# System_Clocks.net
KiCad netlist of a schematic drawn in Altium Designer
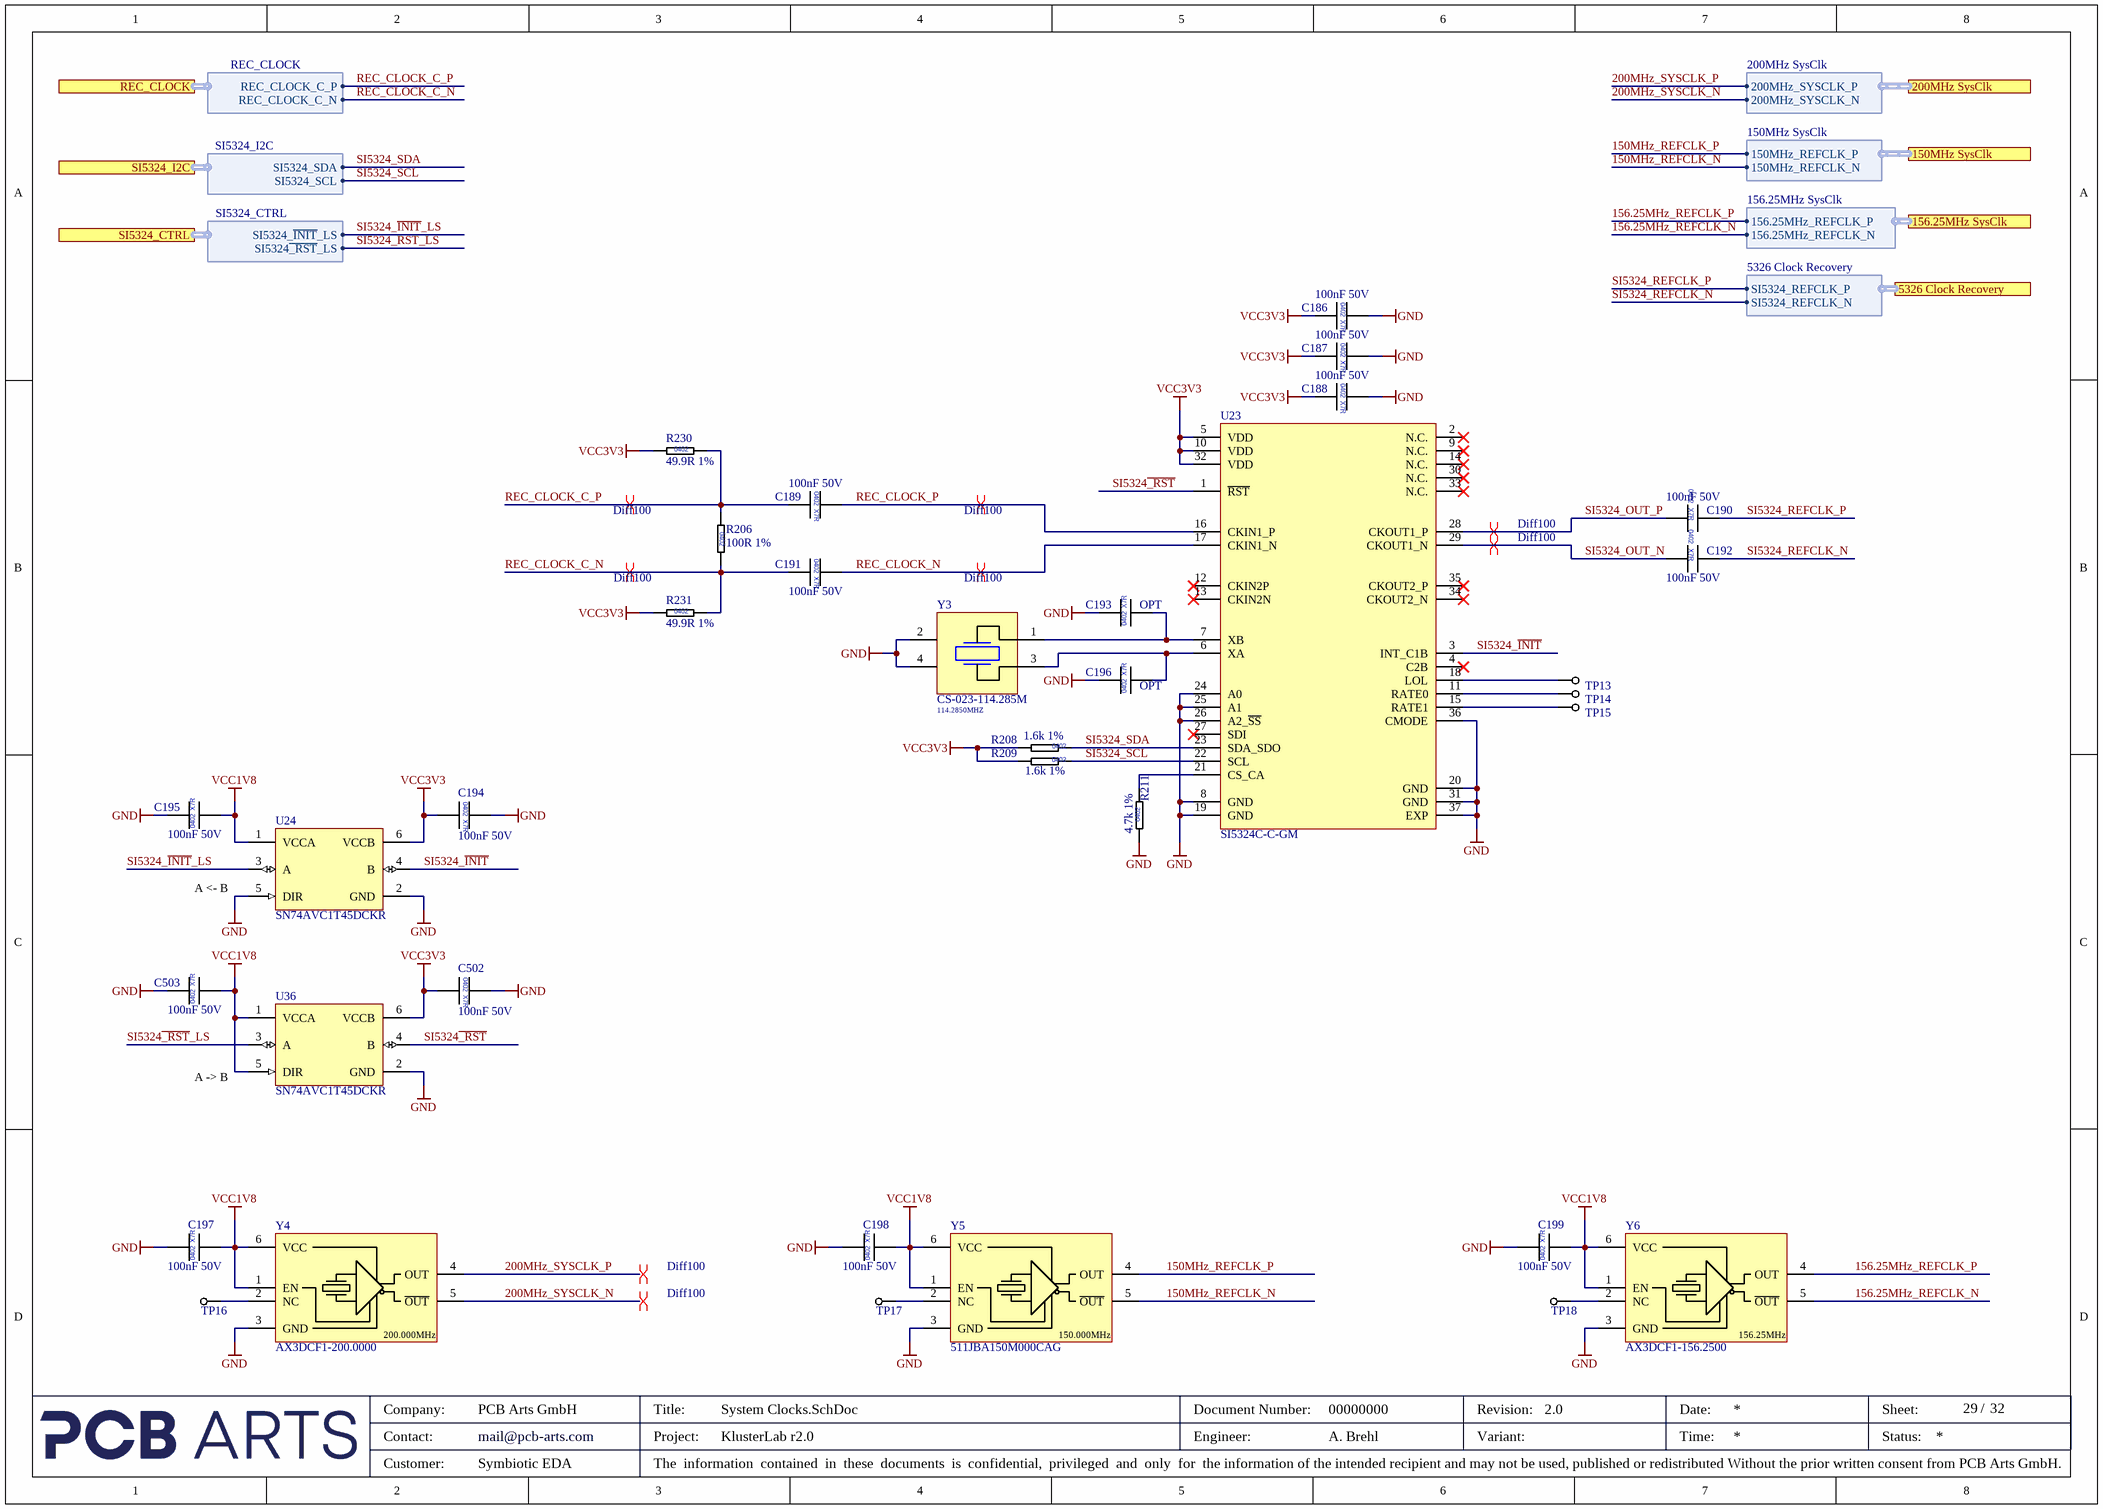
[diagram p0: System Clocks.SchDoc]

(export (version "E")
  (design (tool "Eeschema 10.0.6"))
  (components
    (comp (ref "C186")
      (value "100nF 50V")
      (footprint "Cap:CAP_0402_L")
      (description "Multilayer Ceramic Capacitors MLCC - SMD/SMT 0402 50VDC")
      (libsource (lib "") (part "CAP_0402_100nF_50V_1"))
    )
    (comp (ref "C187")
      (value "100nF 50V")
      (footprint "Cap:CAP_0402_L")
      (description "Multilayer Ceramic Capacitors MLCC - SMD/SMT 0402 50VDC")
      (libsource (lib "") (part "CAP_0402_100nF_50V_1"))
    )
    (comp (ref "C188")
      (value "100nF 50V")
      (footprint "Cap:CAP_0402_L")
      (description "Multilayer Ceramic Capacitors MLCC - SMD/SMT 0402 50VDC")
      (libsource (lib "") (part "CAP_0402_100nF_50V_1"))
    )
    (comp (ref "C189")
      (value "100nF 50V")
      (footprint "Cap:CAP_0402_L")
      (description "Multilayer Ceramic Capacitors MLCC - SMD/SMT 0402 50VDC")
      (libsource (lib "") (part "CAP_0402_100nF_50V_1"))
    )
    (comp (ref "C190")
      (value "100nF 50V")
      (footprint "Cap:CAP_0402_L")
      (description "Multilayer Ceramic Capacitors MLCC - SMD/SMT 0402 50VDC")
      (libsource (lib "Cap") (part "CAP_0402_100nF_50V"))
    )
    (comp (ref "C191")
      (value "100nF 50V")
      (footprint "Cap:CAP_0402_L")
      (description "Multilayer Ceramic Capacitors MLCC - SMD/SMT 0402 50VDC")
      (libsource (lib "") (part "CAP_0402_100nF_50V_1"))
    )
    (comp (ref "C192")
      (value "100nF 50V")
      (footprint "Cap:CAP_0402_L")
      (description "Multilayer Ceramic Capacitors MLCC - SMD/SMT 0402 50VDC")
      (libsource (lib "Cap") (part "CAP_0402_100nF_50V"))
    )
    (comp (ref "C193")
      (value "OPT")
      (footprint "Cap:CAP_0402_L")
      (description "Multilayer Ceramic Capacitors MLCC - SMD/SMT 0402 Optional Placeholder")
      (libsource (lib "Cap") (part "CAP_0402_OPT"))
    )
    (comp (ref "C194")
      (value "100nF 50V")
      (footprint "Cap:CAP_0402_L")
      (description "Multilayer Ceramic Capacitors MLCC - SMD/SMT 0402 50VDC")
      (libsource (lib "") (part "CAP_0402_100nF_50V_1"))
    )
    (comp (ref "C195")
      (value "100nF 50V")
      (footprint "Cap:CAP_0402_L")
      (description "Multilayer Ceramic Capacitors MLCC - SMD/SMT 0402 50VDC")
      (libsource (lib "Cap") (part "CAP_0402_100nF_50V"))
    )
    (comp (ref "C196")
      (value "OPT")
      (footprint "Cap:CAP_0402_L")
      (description "Multilayer Ceramic Capacitors MLCC - SMD/SMT 0402 Optional Placeholder")
      (libsource (lib "Cap") (part "CAP_0402_OPT"))
    )
    (comp (ref "C197")
      (value "100nF 50V")
      (footprint "Cap:CAP_0402_L")
      (description "Multilayer Ceramic Capacitors MLCC - SMD/SMT 0402 50VDC")
      (libsource (lib "Cap") (part "CAP_0402_100nF_50V"))
    )
    (comp (ref "C198")
      (value "100nF 50V")
      (footprint "Cap:CAP_0402_L")
      (description "Multilayer Ceramic Capacitors MLCC - SMD/SMT 0402 50VDC")
      (libsource (lib "Cap") (part "CAP_0402_100nF_50V"))
    )
    (comp (ref "C199")
      (value "100nF 50V")
      (footprint "Cap:CAP_0402_L")
      (description "Multilayer Ceramic Capacitors MLCC - SMD/SMT 0402 50VDC")
      (libsource (lib "Cap") (part "CAP_0402_100nF_50V"))
    )
    (comp (ref "C502")
      (value "100nF 50V")
      (footprint "Cap:CAP_0402_L")
      (description "Multilayer Ceramic Capacitors MLCC - SMD/SMT 0402 50VDC")
      (libsource (lib "") (part "CAP_0402_100nF_50V_1"))
    )
    (comp (ref "C503")
      (value "100nF 50V")
      (footprint "Cap:CAP_0402_L")
      (description "Multilayer Ceramic Capacitors MLCC - SMD/SMT 0402 50VDC")
      (libsource (lib "Cap") (part "CAP_0402_100nF_50V"))
    )
    (comp (ref "R206")
      (value "100R 1%")
      (footprint "Res:RES_0402_L")
      (description "Thick Film Resistors - SMD 100Ohm 1%")
      (libsource (lib "Res") (part "RES_0402_100R_1%"))
    )
    (comp (ref "R208")
      (value "1.6k 1%")
      (footprint "Res:RES_0402_L")
      (description "Thick Film Resistors - SMD 1.6kOhm 1%")
      (libsource (lib "Res") (part "RES_0402_1.6k_1%"))
    )
    (comp (ref "R209")
      (value "1.6k 1%")
      (footprint "Res:RES_0402_L")
      (description "Thick Film Resistors - SMD 1.6kOhm 1%")
      (libsource (lib "Res") (part "RES_0402_1.6k_1%"))
    )
    (comp (ref "R211")
      (value "4.7k 1%")
      (footprint "Res:RES_0402_L")
      (description "Thick Film Resistors - SMD 4.7kOhm 1%")
      (libsource (lib "Res") (part "RES_0402_4.7k_1%"))
    )
    (comp (ref "R230")
      (value "49.9R 1%")
      (footprint "Res:RES_0402_L")
      (description "Thick Film Resistors - SMD 49.9Ohm 1%")
      (libsource (lib "Res") (part "RES_0402_49.9R_1%"))
    )
    (comp (ref "R231")
      (value "49.9R 1%")
      (footprint "Res:RES_0402_L")
      (description "Thick Film Resistors - SMD 49.9Ohm 1%")
      (libsource (lib "Res") (part "RES_0402_49.9R_1%"))
    )
    (comp (ref "TP13")
      (value "Testpoint")
      (footprint "Electro_mech:Testpoint 0.8mm")
      (description "Testpoint 0.8mm")
      (libsource (lib "Electro_Mech") (part "Testpoint 0.8mm"))
    )
    (comp (ref "TP14")
      (value "Testpoint")
      (footprint "Electro_mech:Testpoint 0.8mm")
      (description "Testpoint 0.8mm")
      (libsource (lib "Electro_Mech") (part "Testpoint 0.8mm"))
    )
    (comp (ref "TP15")
      (value "Testpoint")
      (footprint "Electro_mech:Testpoint 0.8mm")
      (description "Testpoint 0.8mm")
      (libsource (lib "Electro_Mech") (part "Testpoint 0.8mm"))
    )
    (comp (ref "TP16")
      (value "Testpoint")
      (footprint "Electro_mech:Testpoint 0.8mm")
      (description "Testpoint 0.8mm")
      (libsource (lib "Electro_Mech") (part "Testpoint 0.8mm"))
    )
    (comp (ref "TP17")
      (value "Testpoint")
      (footprint "Electro_mech:Testpoint 0.8mm")
      (description "Testpoint 0.8mm")
      (libsource (lib "Electro_Mech") (part "Testpoint 0.8mm"))
    )
    (comp (ref "TP18")
      (value "Testpoint")
      (footprint "Electro_mech:Testpoint 0.8mm")
      (description "Testpoint 0.8mm")
      (libsource (lib "Electro_Mech") (part "Testpoint 0.8mm"))
    )
    (comp (ref "U23")
      (value "SI5324C-C-GM")
      (footprint "Timer:QFN50P600X600X85-37N")
      (description "PRECISION CLOCK MULTIPLIER/ JITTER ATTENUATOR")
      (libsource (lib "Timer") (part "SI5324C-C-GM_PRECISION CLOCK MULTIPLIER/ JITTER ATTENUATOR"))
    )
    (comp (ref "U24")
      (value "SN74AVC1T45DCKR")
      (footprint "Digital:SOT65P210X100-6N")
      (description "Single-Bit Dual-Supply Bus Transceiver with Configurable Voltage Translation and 3-State Outputs")
      (libsource (lib "Digital") (part "SN74AVC1T45DCKR_Single-Bit Dual-Supply Bus Transceiver"))
    )
    (comp (ref "U36")
      (value "SN74AVC1T45DCKR")
      (footprint "Digital:SOT65P210X100-6N")
      (description "Single-Bit Dual-Supply Bus Transceiver with Configurable Voltage Translation and 3-State Outputs")
      (libsource (lib "Digital") (part "SN74AVC1T45DCKR_Single-Bit Dual-Supply Bus Transceiver"))
    )
    (comp (ref "Y3")
      (value "CS-023-114.285M")
      (footprint "Timer:S3D - Shenzhen SCTF Elec")
      (description "3.2 x 2.5 x 0.8 mm SMD Crystal")
      (fields (field (name "FREQUENCY") "114.2850MHZ"))
      (libsource (lib "Timer") (part "Quarz 114.2850MHz ESR 80R 18pF"))
    )
    (comp (ref "Y4")
      (value "AX3DCF1-200.0000")
      (footprint "Timer:Abracon AX3")
      (description "200MHz Clock Oscillator, 1V8, LVDS")
      (libsource (lib "Timer") (part "AX3DCF1-200.0000_200MHz Clock Oscillator, 1V8, LVDS"))
    )
    (comp (ref "Y5")
      (value "511JBA150M000CAG")
      (footprint "Timer:Abracon AX3")
      (description "150MHz Clock Oscillator, 1V8, LVDS")
      (libsource (lib "Timer") (part "511JBA150M000CAG_150MHz Clock Oscillator, 1V8, LVDS"))
    )
    (comp (ref "Y6")
      (value "AX3DCF1-156.2500")
      (footprint "Timer:Abracon AX3")
      (description "156.25MHz Clock Oscillator, 1V8, LVDS")
      (libsource (lib "Timer") (part "AX3DCF1-156.2500_156.25MHz Clock Oscillator, 1V8, LVDS"))
    )
  )
  (nets
    (net (code "11") (name "/150MHz_REFCLK_N") (class "Default")
      (node (ref "Y5") (pin "5") (pinfunction "~{OUT}_5") (pintype "passive"))
    )
    (net (code "12") (name "/150MHz_REFCLK_P") (class "Default")
      (node (ref "Y5") (pin "4") (pinfunction "OUT_4") (pintype "passive"))
    )
    (net (code "13") (name "/156.25MHz_REFCLK_N") (class "Default")
      (node (ref "Y6") (pin "5") (pinfunction "~{OUT}_5") (pintype "passive"))
    )
    (net (code "14") (name "/156.25MHz_REFCLK_P") (class "Default")
      (node (ref "Y6") (pin "4") (pinfunction "OUT_4") (pintype "passive"))
    )
    (net (code "15") (name "/200MHz_SYSCLK_N") (class "Default")
      (node (ref "Y4") (pin "5") (pinfunction "~{OUT}_5") (pintype "passive"))
    )
    (net (code "16") (name "/200MHz_SYSCLK_P") (class "Default")
      (node (ref "Y4") (pin "4") (pinfunction "OUT_4") (pintype "passive"))
    )
    (net (code "17") (name "/REC_CLOCK_C_N") (class "Default")
      (node (ref "C191") (pin "2") (pinfunction "2_2") (pintype "passive"))
      (node (ref "R206") (pin "2") (pinfunction "2_2") (pintype "passive"))
      (node (ref "R231") (pin "2") (pinfunction "2_2") (pintype "passive"))
    )
    (net (code "18") (name "/REC_CLOCK_C_P") (class "Default")
      (node (ref "C189") (pin "2") (pinfunction "2_2") (pintype "passive"))
      (node (ref "R206") (pin "1") (pinfunction "1_1") (pintype "passive"))
      (node (ref "R230") (pin "2") (pinfunction "2_2") (pintype "passive"))
    )
    (net (code "19") (name "/REC_CLOCK_N") (class "Default")
      (node (ref "C191") (pin "1") (pinfunction "1_1") (pintype "passive"))
      (node (ref "U23") (pin "17") (pinfunction "CKIN1_N_17") (pintype "passive"))
    )
    (net (code "20") (name "/REC_CLOCK_P") (class "Default")
      (node (ref "C189") (pin "1") (pinfunction "1_1") (pintype "passive"))
      (node (ref "U23") (pin "16") (pinfunction "CKIN1_P_16") (pintype "passive"))
    )
    (net (code "21") (name "/SI5324_OUT_N") (class "Default")
      (node (ref "C192") (pin "1") (pinfunction "1_1") (pintype "passive"))
      (node (ref "U23") (pin "29") (pinfunction "CKOUT1_N_29") (pintype "passive"))
    )
    (net (code "22") (name "/SI5324_OUT_P") (class "Default")
      (node (ref "C190") (pin "1") (pinfunction "1_1") (pintype "passive"))
      (node (ref "U23") (pin "28") (pinfunction "CKOUT1_P_28") (pintype "passive"))
    )
    (net (code "23") (name "/SI5324_REFCLK_N") (class "Default")
      (node (ref "C192") (pin "2") (pinfunction "2_2") (pintype "passive"))
    )
    (net (code "24") (name "/SI5324_REFCLK_P") (class "Default")
      (node (ref "C190") (pin "2") (pinfunction "2_2") (pintype "passive"))
    )
    (net (code "25") (name "/SI5324_SCL") (class "Default")
      (node (ref "R209") (pin "1") (pinfunction "1_1") (pintype "passive"))
      (node (ref "U23") (pin "22") (pinfunction "SCL_22") (pintype "passive"))
    )
    (net (code "26") (name "/SI5324_SDA") (class "Default")
      (node (ref "R208") (pin "1") (pinfunction "1_1") (pintype "passive"))
      (node (ref "U23") (pin "23") (pinfunction "SDA_SDO_23") (pintype "passive"))
    )
    (net (code "27") (name "/SI5324_~{INIT}") (class "Default")
      (node (ref "U23") (pin "3") (pinfunction "INT_C1B_3") (pintype "passive"))
      (node (ref "U24") (pin "4") (pinfunction "B_4") (pintype "bidirectional"))
    )
    (net (code "28") (name "/SI5324_~{INIT}_LS") (class "Default")
      (node (ref "U24") (pin "3") (pinfunction "A_3") (pintype "bidirectional"))
    )
    (net (code "29") (name "/SI5324~{_RST}") (class "Default")
      (node (ref "U23") (pin "1") (pinfunction "~{RST}_1") (pintype "passive"))
      (node (ref "U36") (pin "4") (pinfunction "B_4") (pintype "bidirectional"))
    )
    (net (code "30") (name "/SI5324~{_RST}_LS") (class "Default")
      (node (ref "U36") (pin "3") (pinfunction "A_3") (pintype "bidirectional"))
    )
    (net (code "38") (name "GND") (class "Default")
      (node (ref "C186") (pin "1") (pinfunction "1_1") (pintype "passive"))
      (node (ref "C187") (pin "1") (pinfunction "1_1") (pintype "passive"))
      (node (ref "C188") (pin "1") (pinfunction "1_1") (pintype "passive"))
      (node (ref "C193") (pin "1") (pinfunction "1_1") (pintype "passive"))
      (node (ref "C194") (pin "1") (pinfunction "1_1") (pintype "passive"))
      (node (ref "C195") (pin "1") (pinfunction "1_1") (pintype "passive"))
      (node (ref "C196") (pin "1") (pinfunction "1_1") (pintype "passive"))
      (node (ref "C197") (pin "1") (pinfunction "1_1") (pintype "passive"))
      (node (ref "C198") (pin "1") (pinfunction "1_1") (pintype "passive"))
      (node (ref "C199") (pin "1") (pinfunction "1_1") (pintype "passive"))
      (node (ref "C502") (pin "1") (pinfunction "1_1") (pintype "passive"))
      (node (ref "C503") (pin "1") (pinfunction "1_1") (pintype "passive"))
      (node (ref "R211") (pin "1") (pinfunction "1_1") (pintype "passive"))
      (node (ref "U23") (pin "19") (pinfunction "GND_19") (pintype "passive"))
      (node (ref "U23") (pin "20") (pinfunction "GND_20") (pintype "passive"))
      (node (ref "U23") (pin "24") (pinfunction "A0_24") (pintype "passive"))
      (node (ref "U23") (pin "25") (pinfunction "A1_25") (pintype "passive"))
      (node (ref "U23") (pin "26") (pinfunction "A2_~{SS}_26") (pintype "passive"))
      (node (ref "U23") (pin "31") (pinfunction "GND_31") (pintype "passive"))
      (node (ref "U23") (pin "36") (pinfunction "CMODE_36") (pintype "passive"))
      (node (ref "U23") (pin "37") (pinfunction "EXP_37") (pintype "passive"))
      (node (ref "U23") (pin "8") (pinfunction "GND_8") (pintype "passive"))
      (node (ref "U24") (pin "2") (pinfunction "GND_2") (pintype "passive"))
      (node (ref "U24") (pin "5") (pinfunction "DIR_5") (pintype "input"))
      (node (ref "U36") (pin "2") (pinfunction "GND_2") (pintype "passive"))
      (node (ref "Y3") (pin "2") (pinfunction "2_2") (pintype "passive"))
      (node (ref "Y3") (pin "4") (pinfunction "4_4") (pintype "passive"))
      (node (ref "Y4") (pin "3") (pinfunction "GND_3") (pintype "passive"))
      (node (ref "Y5") (pin "3") (pinfunction "GND_3") (pintype "passive"))
      (node (ref "Y6") (pin "3") (pinfunction "GND_3") (pintype "passive"))
    )
    (net (code "39") (name "Net-(TP13-GND)") (class "Default")
      (node (ref "TP13") (pin "1") (pinfunction "GND_1") (pintype "passive"))
      (node (ref "U23") (pin "18") (pinfunction "LOL_18") (pintype "passive"))
    )
    (net (code "40") (name "Net-(TP14-GND)") (class "Default")
      (node (ref "TP14") (pin "1") (pinfunction "GND_1") (pintype "passive"))
      (node (ref "U23") (pin "11") (pinfunction "RATE0_11") (pintype "passive"))
    )
    (net (code "41") (name "Net-(TP15-GND)") (class "Default")
      (node (ref "TP15") (pin "1") (pinfunction "GND_1") (pintype "passive"))
      (node (ref "U23") (pin "15") (pinfunction "RATE1_15") (pintype "passive"))
    )
    (net (code "42") (name "Net-(TP16-GND)") (class "Default")
      (node (ref "TP16") (pin "1") (pinfunction "GND_1") (pintype "passive"))
      (node (ref "Y4") (pin "2") (pinfunction "NC_2") (pintype "passive"))
    )
    (net (code "43") (name "Net-(TP17-GND)") (class "Default")
      (node (ref "TP17") (pin "1") (pinfunction "GND_1") (pintype "passive"))
      (node (ref "Y5") (pin "2") (pinfunction "NC_2") (pintype "passive"))
    )
    (net (code "44") (name "Net-(TP18-GND)") (class "Default")
      (node (ref "TP18") (pin "1") (pinfunction "GND_1") (pintype "passive"))
      (node (ref "Y6") (pin "2") (pinfunction "NC_2") (pintype "passive"))
    )
    (net (code "45") (name "Net-(U23-CS_CA)") (class "Default")
      (node (ref "R211") (pin "2") (pinfunction "2_2") (pintype "passive"))
      (node (ref "U23") (pin "21") (pinfunction "CS_CA_21") (pintype "passive"))
    )
    (net (code "46") (name "Net-(U23-XA)") (class "Default")
      (node (ref "C196") (pin "2") (pinfunction "2_2") (pintype "passive"))
      (node (ref "U23") (pin "6") (pinfunction "XA_6") (pintype "passive"))
      (node (ref "Y3") (pin "3") (pinfunction "3_3") (pintype "passive"))
    )
    (net (code "47") (name "Net-(U23-XB)") (class "Default")
      (node (ref "C193") (pin "2") (pinfunction "2_2") (pintype "passive"))
      (node (ref "U23") (pin "7") (pinfunction "XB_7") (pintype "passive"))
      (node (ref "Y3") (pin "1") (pinfunction "1_1") (pintype "passive"))
    )
    (net (code "48") (name "VCC1V8") (class "Default")
      (node (ref "C195") (pin "2") (pinfunction "2_2") (pintype "passive"))
      (node (ref "C197") (pin "2") (pinfunction "2_2") (pintype "passive"))
      (node (ref "C198") (pin "2") (pinfunction "2_2") (pintype "passive"))
      (node (ref "C199") (pin "2") (pinfunction "2_2") (pintype "passive"))
      (node (ref "C503") (pin "2") (pinfunction "2_2") (pintype "passive"))
      (node (ref "U24") (pin "1") (pinfunction "VCCA_1") (pintype "passive"))
      (node (ref "U36") (pin "1") (pinfunction "VCCA_1") (pintype "passive"))
      (node (ref "U36") (pin "5") (pinfunction "DIR_5") (pintype "input"))
      (node (ref "Y4") (pin "1") (pinfunction "EN_1") (pintype "passive"))
      (node (ref "Y4") (pin "6") (pinfunction "VCC_6") (pintype "passive"))
      (node (ref "Y5") (pin "1") (pinfunction "EN_1") (pintype "passive"))
      (node (ref "Y5") (pin "6") (pinfunction "VCC_6") (pintype "passive"))
      (node (ref "Y6") (pin "1") (pinfunction "EN_1") (pintype "passive"))
      (node (ref "Y6") (pin "6") (pinfunction "VCC_6") (pintype "passive"))
    )
    (net (code "49") (name "VCC3V3") (class "Default")
      (node (ref "C186") (pin "2") (pinfunction "2_2") (pintype "passive"))
      (node (ref "C187") (pin "2") (pinfunction "2_2") (pintype "passive"))
      (node (ref "C188") (pin "2") (pinfunction "2_2") (pintype "passive"))
      (node (ref "C194") (pin "2") (pinfunction "2_2") (pintype "passive"))
      (node (ref "C502") (pin "2") (pinfunction "2_2") (pintype "passive"))
      (node (ref "R208") (pin "2") (pinfunction "2_2") (pintype "passive"))
      (node (ref "R209") (pin "2") (pinfunction "2_2") (pintype "passive"))
      (node (ref "R230") (pin "1") (pinfunction "1_1") (pintype "passive"))
      (node (ref "R231") (pin "1") (pinfunction "1_1") (pintype "passive"))
      (node (ref "U23") (pin "10") (pinfunction "VDD_10") (pintype "passive"))
      (node (ref "U23") (pin "32") (pinfunction "VDD_32") (pintype "passive"))
      (node (ref "U23") (pin "5") (pinfunction "VDD_5") (pintype "passive"))
      (node (ref "U24") (pin "6") (pinfunction "VCCB_6") (pintype "passive"))
      (node (ref "U36") (pin "6") (pinfunction "VCCB_6") (pintype "passive"))
    )
    (net (code "50") (name "unconnected-(U23-C2B-Pad4)") (class "Default")
      (node (ref "U23") (pin "4") (pinfunction "C2B_4") (pintype "passive+no_connect"))
    )
    (net (code "51") (name "unconnected-(U23-CKIN2N-Pad13)") (class "Default")
      (node (ref "U23") (pin "13") (pinfunction "CKIN2N_13") (pintype "passive+no_connect"))
    )
    (net (code "52") (name "unconnected-(U23-CKIN2P-Pad12)") (class "Default")
      (node (ref "U23") (pin "12") (pinfunction "CKIN2P_12") (pintype "passive+no_connect"))
    )
    (net (code "53") (name "unconnected-(U23-CKOUT2_N-Pad34)") (class "Default")
      (node (ref "U23") (pin "34") (pinfunction "CKOUT2_N_34") (pintype "passive+no_connect"))
    )
    (net (code "54") (name "unconnected-(U23-CKOUT2_P-Pad35)") (class "Default")
      (node (ref "U23") (pin "35") (pinfunction "CKOUT2_P_35") (pintype "passive+no_connect"))
    )
    (net (code "55") (name "unconnected-(U23-N.C.-Pad2)") (class "Default")
      (node (ref "U23") (pin "2") (pinfunction "N.C._2") (pintype "passive+no_connect"))
    )
    (net (code "56") (name "unconnected-(U23-N.C.-Pad9)") (class "Default")
      (node (ref "U23") (pin "9") (pinfunction "N.C._9") (pintype "passive+no_connect"))
    )
    (net (code "57") (name "unconnected-(U23-N.C.-Pad14)") (class "Default")
      (node (ref "U23") (pin "14") (pinfunction "N.C._14") (pintype "passive+no_connect"))
    )
    (net (code "58") (name "unconnected-(U23-N.C.-Pad30)") (class "Default")
      (node (ref "U23") (pin "30") (pinfunction "N.C._30") (pintype "passive+no_connect"))
    )
    (net (code "59") (name "unconnected-(U23-N.C.-Pad33)") (class "Default")
      (node (ref "U23") (pin "33") (pinfunction "N.C._33") (pintype "passive+no_connect"))
    )
    (net (code "60") (name "unconnected-(U23-SDI-Pad27)") (class "Default")
      (node (ref "U23") (pin "27") (pinfunction "SDI_27") (pintype "passive+no_connect"))
    )
  )
)
